# PG03_ECG.net
KiCad netlist of a schematic drawn in Altium Designer
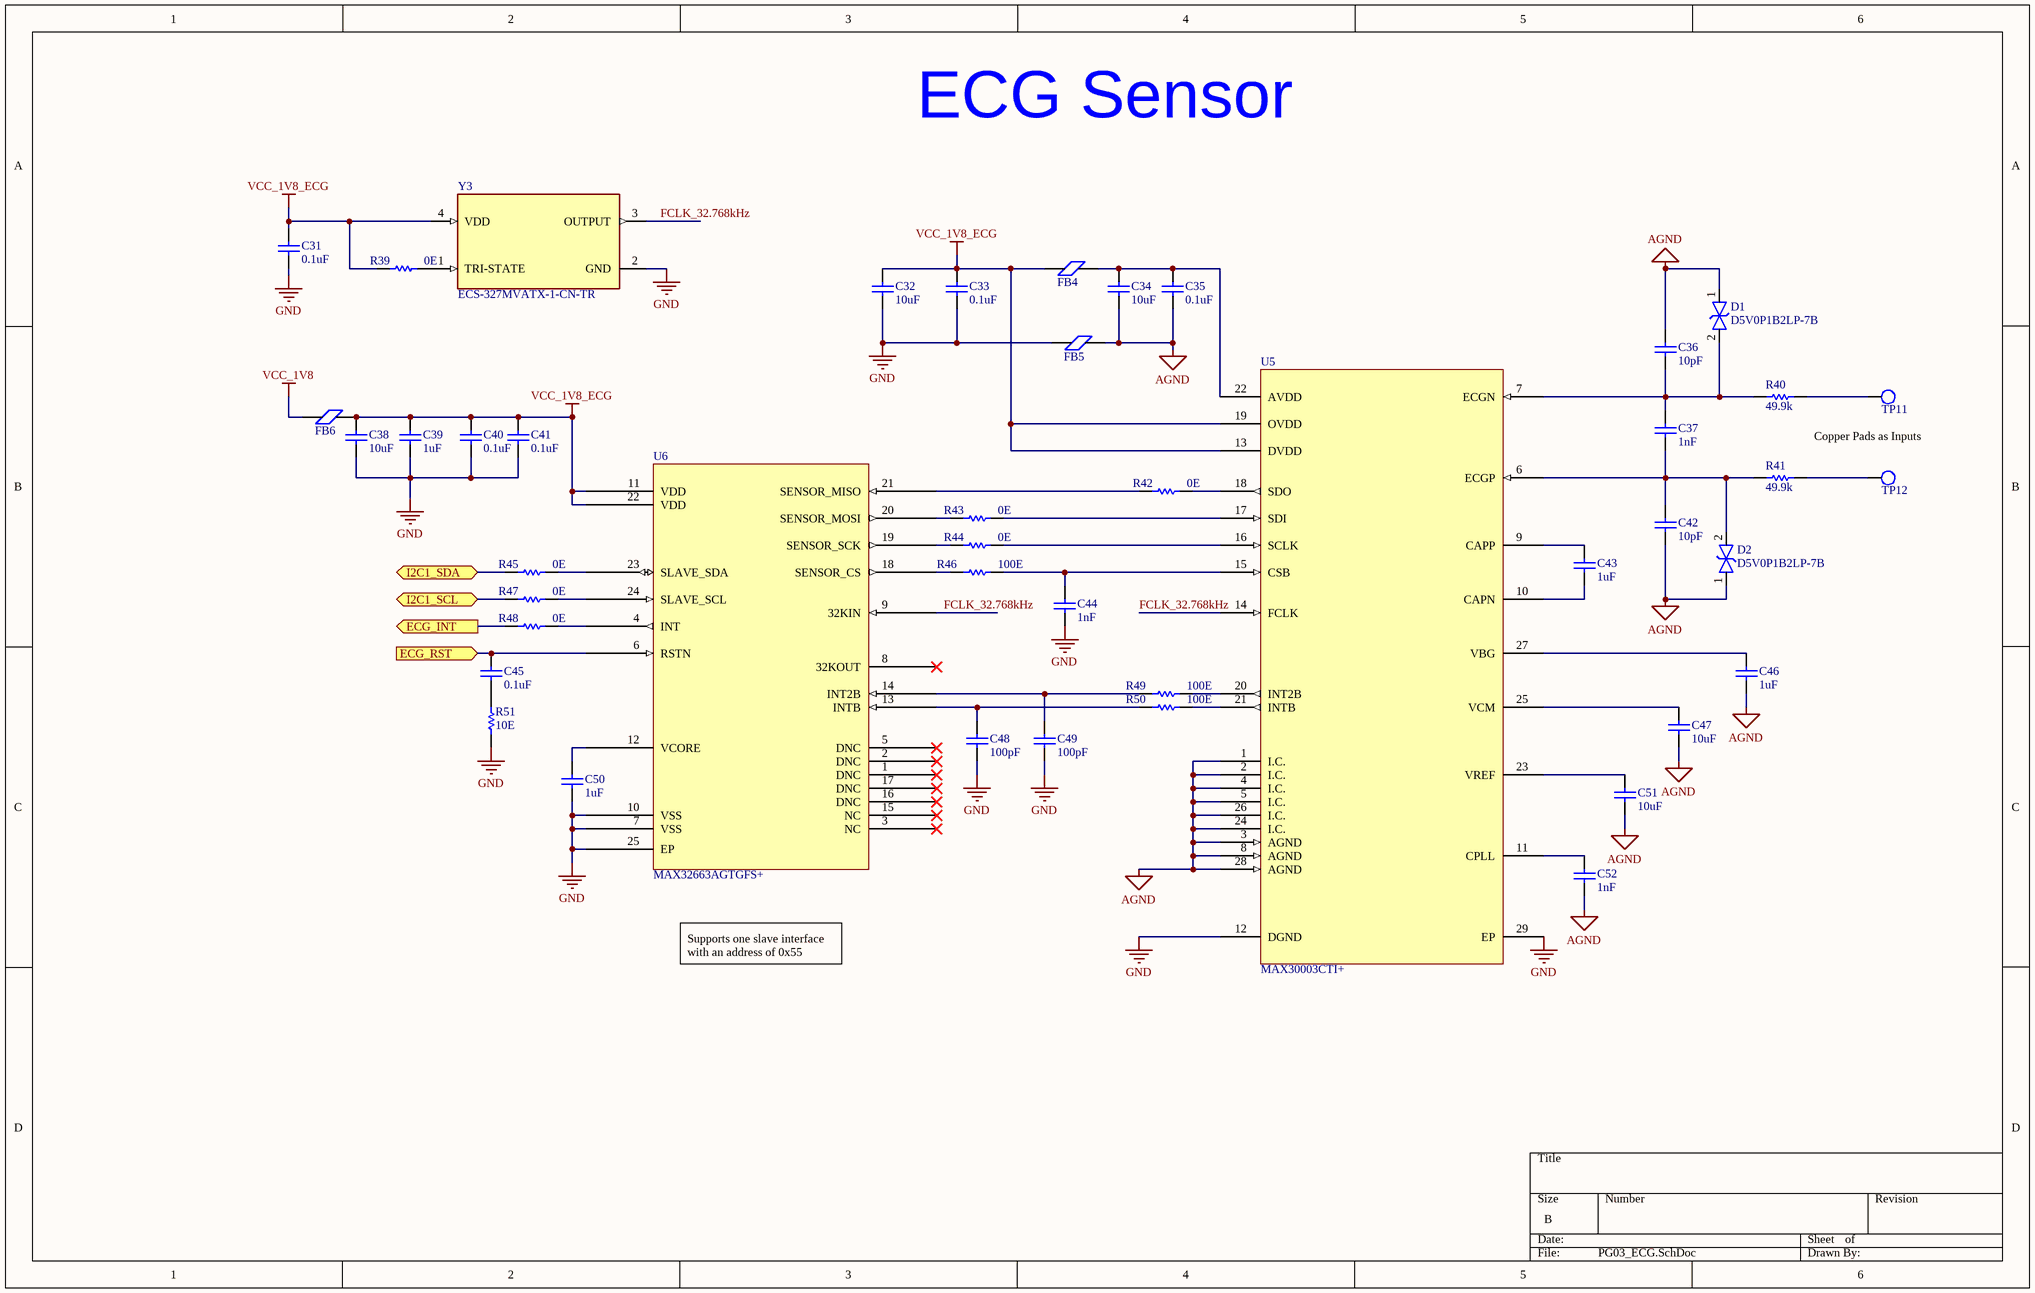
[diagram p0: PG03_ECG.SchDoc]

(export (version "E")
  (design (tool "Eeschema 10.0.6"))
  (components
    (comp (ref "C31")
      (value "0.1uF")
      (footprint "0402C")
      (description "CAP CER 0.1UF 50V X7R 0402")
      (libsource (lib "Smart Ring Components") (part "CAP_0402_0.1uF_50V"))
    )
    (comp (ref "C32")
      (value "10uF")
      (footprint "0805C")
      (description "CAP CER 10UF 16V X7R 0805")
      (libsource (lib "Smart Ring Components") (part "CAP_0805_10uF_16V"))
    )
    (comp (ref "C33")
      (value "0.1uF")
      (footprint "0402C")
      (description "CAP CER 0.1UF 50V X7R 0402")
      (libsource (lib "Smart Ring Components") (part "CAP_0402_0.1uF_50V"))
    )
    (comp (ref "C34")
      (value "10uF")
      (footprint "0805C")
      (description "CAP CER 10UF 16V X7R 0805")
      (libsource (lib "Smart Ring Components") (part "CAP_0805_10uF_16V"))
    )
    (comp (ref "C35")
      (value "0.1uF")
      (footprint "0402C")
      (description "CAP CER 0.1UF 50V X7R 0402")
      (libsource (lib "Smart Ring Components") (part "CAP_0402_0.1uF_50V"))
    )
    (comp (ref "C36")
      (value "10pF")
      (footprint "0402C")
      (description "CAP CER 10PF 50V C0G/NP0 0402")
      (libsource (lib "Smart Ring Components") (part "CAP_0402_10pF_50V"))
    )
    (comp (ref "C37")
      (value "1nF")
      (footprint "0402C")
      (description "CAP CER 1000PF 50V X7R 0402")
      (libsource (lib "Smart Ring Components") (part "CAP_0402_1nF_50V"))
    )
    (comp (ref "C38")
      (value "10uF")
      (footprint "0805C")
      (description "CAP CER 10UF 16V X7R 0805")
      (libsource (lib "Smart Ring Components") (part "CAP_0805_10uF_16V"))
    )
    (comp (ref "C39")
      (value "1uF")
      (footprint "0805C")
      (description "CAP CER 1UF 25V X7R 0805")
      (libsource (lib "Smart Ring Components") (part "CAP_0805_1uF_25V"))
    )
    (comp (ref "C40")
      (value "0.1uF")
      (footprint "0402C")
      (description "CAP CER 0.1UF 50V X7R 0402")
      (libsource (lib "Smart Ring Components") (part "CAP_0402_0.1uF_50V"))
    )
    (comp (ref "C41")
      (value "0.1uF")
      (footprint "0402C")
      (description "CAP CER 0.1UF 50V X7R 0402")
      (libsource (lib "Smart Ring Components") (part "CAP_0402_0.1uF_50V"))
    )
    (comp (ref "C42")
      (value "10pF")
      (footprint "0402C")
      (description "CAP CER 10PF 50V C0G/NP0 0402")
      (libsource (lib "Smart Ring Components") (part "CAP_0402_10pF_50V"))
    )
    (comp (ref "C43")
      (value "1uF")
      (footprint "0805C")
      (description "CAP CER 1UF 25V X7R 0805")
      (libsource (lib "Smart Ring Components") (part "CAP_0805_1uF_25V"))
    )
    (comp (ref "C44")
      (value "1nF")
      (footprint "0402C")
      (description "CAP CER 1000PF 50V X7R 0402")
      (libsource (lib "Smart Ring Components") (part "CAP_0402_1nF_50V"))
    )
    (comp (ref "C45")
      (value "0.1uF")
      (footprint "0402C")
      (description "CAP CER 0.1UF 50V X7R 0402")
      (libsource (lib "Smart Ring Components") (part "CAP_0402_0.1uF_50V"))
    )
    (comp (ref "C46")
      (value "1uF")
      (footprint "0805C")
      (description "CAP CER 1UF 25V X7R 0805")
      (libsource (lib "Smart Ring Components") (part "CAP_0805_1uF_25V"))
    )
    (comp (ref "C47")
      (value "10uF")
      (footprint "0805C")
      (description "CAP CER 10UF 16V X7R 0805")
      (libsource (lib "Smart Ring Components") (part "CAP_0805_10uF_16V"))
    )
    (comp (ref "C48")
      (value "100pF")
      (footprint "0402C")
      (description "CAP CER 100PF 50V C0G 0402")
      (libsource (lib "Smart Ring Components") (part "CAP_0402_100pF_50V"))
    )
    (comp (ref "C49")
      (value "100pF")
      (footprint "0402C")
      (description "CAP CER 100PF 50V C0G 0402")
      (libsource (lib "Smart Ring Components") (part "CAP_0402_100pF_50V"))
    )
    (comp (ref "C50")
      (value "1uF")
      (footprint "0805C")
      (description "CAP CER 1UF 25V X7R 0805")
      (libsource (lib "Smart Ring Components") (part "CAP_0805_1uF_25V"))
    )
    (comp (ref "C51")
      (value "10uF")
      (footprint "0805C")
      (description "CAP CER 10UF 16V X7R 0805")
      (libsource (lib "Smart Ring Components") (part "CAP_0805_10uF_16V"))
    )
    (comp (ref "C52")
      (value "1nF")
      (footprint "0402C")
      (description "CAP CER 1000PF 50V X7R 0402")
      (libsource (lib "Smart Ring Components") (part "CAP_0402_1nF_50V"))
    )
    (comp (ref "D1")
      (value "D5V0P1B2LP-7B")
      (footprint "D5V0P1B2LP-7B")
      (description "TVS DIODE 5.5VWM 13VC DFN1006-2")
      (fields (field (name "MFR") "Diodes Incorporated"))
      (libsource (lib "Smart Ring Components") (part "TVS_D5V0P1B2LP-7B"))
    )
    (comp (ref "D2")
      (value "D5V0P1B2LP-7B")
      (footprint "D5V0P1B2LP-7B")
      (description "TVS DIODE 5.5VWM 13VC DFN1006-2")
      (fields (field (name "MFR") "Diodes Incorporated"))
      (libsource (lib "Smart Ring Components") (part "TVS_D5V0P1B2LP-7B"))
    )
    (comp (ref "FB4")
      (value "Ferrite Bead")
      (footprint "0402R")
      (description "CHIP BEAD 600 OHM 0402 300mA")
      (fields (field (name "MFR") "Walsin") (field (name "MPN") "WLBD1005K2U601TP"))
      (libsource (lib "Smart Ring Components") (part "Ferrite Bead"))
    )
    (comp (ref "FB5")
      (value "Ferrite Bead")
      (footprint "0402R")
      (description "CHIP BEAD 600 OHM 0402 300mA")
      (fields (field (name "MFR") "Walsin") (field (name "MPN") "WLBD1005K2U601TP"))
      (libsource (lib "Smart Ring Components") (part "Ferrite Bead"))
    )
    (comp (ref "FB6")
      (value "Ferrite Bead")
      (footprint "0402R")
      (description "CHIP BEAD 600 OHM 0402 300mA")
      (fields (field (name "MFR") "Walsin") (field (name "MPN") "WLBD1005K2U601TP"))
      (libsource (lib "Smart Ring Components") (part "Ferrite Bead"))
    )
    (comp (ref "R39")
      (value "0E")
      (footprint "0402R")
      (description "RES 0 OHM JUMPER 1/16W 0402")
      (fields (field (name "MFR") "Generic"))
      (libsource (lib "Smart Ring Components") (part "RES_0402_0E"))
    )
    (comp (ref "R40")
      (value "49.9k")
      (footprint "0402R")
      (description "RES 49.9K OHM 1% 1/16W 0402")
      (fields (field (name "MFR") "Generic"))
      (libsource (lib "Smart Ring Components") (part "RES_0402_49.9k"))
    )
    (comp (ref "R41")
      (value "49.9k")
      (footprint "0402R")
      (description "RES 49.9K OHM 1% 1/16W 0402")
      (fields (field (name "MFR") "Generic"))
      (libsource (lib "Smart Ring Components") (part "RES_0402_49.9k"))
    )
    (comp (ref "R42")
      (value "0E")
      (footprint "0402R")
      (description "RES 0 OHM JUMPER 1/16W 0402")
      (fields (field (name "MFR") "Generic"))
      (libsource (lib "Smart Ring Components") (part "RES_0402_0E"))
    )
    (comp (ref "R43")
      (value "0E")
      (footprint "0402R")
      (description "RES 0 OHM JUMPER 1/16W 0402")
      (fields (field (name "MFR") "Generic"))
      (libsource (lib "Smart Ring Components") (part "RES_0402_0E"))
    )
    (comp (ref "R44")
      (value "0E")
      (footprint "0402R")
      (description "RES 0 OHM JUMPER 1/16W 0402")
      (fields (field (name "MFR") "Generic"))
      (libsource (lib "Smart Ring Components") (part "RES_0402_0E"))
    )
    (comp (ref "R45")
      (value "0E")
      (footprint "0402R")
      (description "RES 0 OHM JUMPER 1/16W 0402")
      (fields (field (name "MFR") "Generic"))
      (libsource (lib "Smart Ring Components") (part "RES_0402_0E"))
    )
    (comp (ref "R46")
      (value "100E")
      (footprint "0402R")
      (description "RES 100 OHM 1% 1/16W 0402")
      (fields (field (name "MFR") "Generic"))
      (libsource (lib "Smart Ring Components") (part "RES_0402_100E"))
    )
    (comp (ref "R47")
      (value "0E")
      (footprint "0402R")
      (description "RES 0 OHM JUMPER 1/16W 0402")
      (fields (field (name "MFR") "Generic"))
      (libsource (lib "Smart Ring Components") (part "RES_0402_0E"))
    )
    (comp (ref "R48")
      (value "0E")
      (footprint "0402R")
      (description "RES 0 OHM JUMPER 1/16W 0402")
      (fields (field (name "MFR") "Generic"))
      (libsource (lib "Smart Ring Components") (part "RES_0402_0E"))
    )
    (comp (ref "R49")
      (value "100E")
      (footprint "0402R")
      (description "RES 100 OHM 1% 1/16W 0402")
      (fields (field (name "MFR") "Generic"))
      (libsource (lib "Smart Ring Components") (part "RES_0402_100E"))
    )
    (comp (ref "R50")
      (value "100E")
      (footprint "0402R")
      (description "RES 100 OHM 1% 1/16W 0402")
      (fields (field (name "MFR") "Generic"))
      (libsource (lib "Smart Ring Components") (part "RES_0402_100E"))
    )
    (comp (ref "R51")
      (value "10E")
      (footprint "0402R")
      (description "RES 10 OHM 1% 1/16W 0402")
      (fields (field (name "MFR") "Generic"))
      (libsource (lib "Smart Ring Components") (part "RES_0402_10E"))
    )
    (comp (ref "TP11")
      (value "Test_Point")
      (footprint "TP_SMD")
      (libsource (lib "Smart Ring Components") (part "Test_Point_1"))
    )
    (comp (ref "TP12")
      (value "Test_Point")
      (footprint "TP_SMD")
      (libsource (lib "Smart Ring Components") (part "Test_Point_1"))
    )
    (comp (ref "U5")
      (value "MAX30003CTI+")
      (footprint "MAX30003CTI+")
      (description "Analog Front End - AFE Bio Potential AFE")
      (fields (field (name "MFR") "Maxim Integrated") (field (name "MPN") "MAX30003CTI+"))
      (libsource (lib "Smart Ring Components") (part "MAX30003CTI+"))
    )
    (comp (ref "U6")
      (value "MAX32663AGTGFS+")
      (footprint "MAX32663AGTGFS+")
      (description "SENSOR HUB W/ B-SECUR'S FULL HEA")
      (fields (field (name "MFR") "Maxim Integrated"))
      (libsource (lib "Smart Ring Components") (part "MAX32663AGTGFS+"))
    )
    (comp (ref "Y3")
      (value "ECS-327MVATX-1-CN-TR")
      (footprint "ECS-327MVATX-1-CN-TR")
      (description "XTAL OSC XO 32.768KHZ SMD")
      (fields (field (name "MFR") "ECS Inc."))
      (libsource (lib "Smart Ring Components") (part "OSC_32.768kHz"))
    )
  )
  (nets
    (net (code "1") (name "/ECG_INT") (class "Default")
      (node (ref "R48") (pin "1") (pinfunction "1_1") (pintype "passive"))
    )
    (net (code "2") (name "/ECG_RST") (class "Default")
      (node (ref "C45") (pin "2") (pinfunction "2_2") (pintype "passive"))
      (node (ref "U6") (pin "6") (pinfunction "RSTN_6") (pintype "input"))
    )
    (net (code "3") (name "/FCLK_32.768kHz") (class "Default")
      (node (ref "U5") (pin "14") (pinfunction "FCLK_14") (pintype "input"))
      (node (ref "U6") (pin "9") (pinfunction "32KIN_9") (pintype "input"))
      (node (ref "Y3") (pin "3") (pinfunction "OUTPUT_3") (pintype "output"))
    )
    (net (code "4") (name "/I2C1_SCL") (class "Default")
      (node (ref "R47") (pin "1") (pinfunction "1_1") (pintype "passive"))
    )
    (net (code "5") (name "/I2C1_SDA") (class "Default")
      (node (ref "R45") (pin "1") (pinfunction "1_1") (pintype "passive"))
    )
    (net (code "6") (name "AGND") (class "Default")
      (node (ref "C34") (pin "1") (pinfunction "1_1") (pintype "passive"))
      (node (ref "C35") (pin "1") (pinfunction "1_1") (pintype "passive"))
      (node (ref "C36") (pin "2") (pinfunction "2_2") (pintype "passive"))
      (node (ref "C42") (pin "1") (pinfunction "1_1") (pintype "passive"))
      (node (ref "C46") (pin "1") (pinfunction "1_1") (pintype "passive"))
      (node (ref "C47") (pin "1") (pinfunction "1_1") (pintype "passive"))
      (node (ref "C51") (pin "1") (pinfunction "1_1") (pintype "passive"))
      (node (ref "C52") (pin "1") (pinfunction "1_1") (pintype "passive"))
      (node (ref "D1") (pin "1") (pinfunction "1_1") (pintype "passive"))
      (node (ref "D2") (pin "1") (pinfunction "1_1") (pintype "passive"))
      (node (ref "FB5") (pin "2") (pinfunction "VREF_2") (pintype "passive"))
      (node (ref "U5") (pin "1") (pinfunction "I.C._1") (pintype "passive"))
      (node (ref "U5") (pin "2") (pinfunction "I.C._2") (pintype "passive"))
      (node (ref "U5") (pin "24") (pinfunction "I.C._24") (pintype "passive"))
      (node (ref "U5") (pin "26") (pinfunction "I.C._26") (pintype "power_in"))
      (node (ref "U5") (pin "28") (pinfunction "AGND_28") (pintype "input"))
      (node (ref "U5") (pin "3") (pinfunction "AGND_3") (pintype "input"))
      (node (ref "U5") (pin "4") (pinfunction "I.C._4") (pintype "passive"))
      (node (ref "U5") (pin "5") (pinfunction "I.C._5") (pintype "passive"))
      (node (ref "U5") (pin "8") (pinfunction "AGND_8") (pintype "input"))
    )
    (net (code "7") (name "GND") (class "Default")
      (node (ref "C31") (pin "1") (pinfunction "1_1") (pintype "passive"))
      (node (ref "C32") (pin "1") (pinfunction "1_1") (pintype "passive"))
      (node (ref "C33") (pin "1") (pinfunction "1_1") (pintype "passive"))
      (node (ref "C38") (pin "1") (pinfunction "1_1") (pintype "passive"))
      (node (ref "C39") (pin "1") (pinfunction "1_1") (pintype "passive"))
      (node (ref "C40") (pin "1") (pinfunction "1_1") (pintype "passive"))
      (node (ref "C41") (pin "1") (pinfunction "1_1") (pintype "passive"))
      (node (ref "C44") (pin "1") (pinfunction "1_1") (pintype "passive"))
      (node (ref "C48") (pin "1") (pinfunction "1_1") (pintype "passive"))
      (node (ref "C49") (pin "1") (pinfunction "1_1") (pintype "passive"))
      (node (ref "C50") (pin "1") (pinfunction "1_1") (pintype "passive"))
      (node (ref "FB5") (pin "1") (pinfunction "VREF_1") (pintype "passive"))
      (node (ref "R51") (pin "1") (pinfunction "1_1") (pintype "passive"))
      (node (ref "U5") (pin "12") (pinfunction "DGND_12") (pintype "power_in"))
      (node (ref "U5") (pin "29") (pinfunction "EP_29") (pintype "power_in"))
      (node (ref "U6") (pin "10") (pinfunction "VSS_10") (pintype "power_in"))
      (node (ref "U6") (pin "25") (pinfunction "EP_25") (pintype "power_in"))
      (node (ref "U6") (pin "7") (pinfunction "VSS_7") (pintype "power_in"))
      (node (ref "Y3") (pin "2") (pinfunction "GND_2") (pintype "power_in"))
    )
    (net (code "8") (name "Net-(C45-Pad1)") (class "Default")
      (node (ref "C45") (pin "1") (pinfunction "1_1") (pintype "passive"))
      (node (ref "R51") (pin "2") (pinfunction "2_2") (pintype "passive"))
    )
    (net (code "9") (name "Net-(R40-Pad2)") (class "Default")
      (node (ref "R40") (pin "2") (pinfunction "2_2") (pintype "passive"))
      (node (ref "TP11") (pin "1") (pintype "passive"))
    )
    (net (code "10") (name "Net-(R41-Pad2)") (class "Default")
      (node (ref "R41") (pin "2") (pinfunction "2_2") (pintype "passive"))
      (node (ref "TP12") (pin "1") (pintype "passive"))
    )
    (net (code "11") (name "Net-(U5-AVDD)") (class "Default")
      (node (ref "C34") (pin "2") (pinfunction "2_2") (pintype "passive"))
      (node (ref "C35") (pin "2") (pinfunction "2_2") (pintype "passive"))
      (node (ref "FB4") (pin "1") (pinfunction "VREF_1") (pintype "passive"))
      (node (ref "U5") (pin "22") (pinfunction "AVDD_22") (pintype "power_in"))
    )
    (net (code "12") (name "Net-(U5-CAPN)") (class "Default")
      (node (ref "C43") (pin "1") (pinfunction "1_1") (pintype "passive"))
      (node (ref "U5") (pin "10") (pinfunction "CAPN_10") (pintype "passive"))
    )
    (net (code "13") (name "Net-(U5-CAPP)") (class "Default")
      (node (ref "C43") (pin "2") (pinfunction "2_2") (pintype "passive"))
      (node (ref "U5") (pin "9") (pinfunction "CAPP_9") (pintype "passive"))
    )
    (net (code "14") (name "Net-(U5-CPLL)") (class "Default")
      (node (ref "C52") (pin "2") (pinfunction "2_2") (pintype "passive"))
      (node (ref "U5") (pin "11") (pinfunction "CPLL_11") (pintype "passive"))
    )
    (net (code "15") (name "Net-(U5-CSB)") (class "Default")
      (node (ref "C44") (pin "2") (pinfunction "2_2") (pintype "passive"))
      (node (ref "R46") (pin "2") (pinfunction "2_2") (pintype "passive"))
      (node (ref "U5") (pin "15") (pinfunction "CSB_15") (pintype "input"))
    )
    (net (code "16") (name "Net-(U5-ECGN)") (class "Default")
      (node (ref "C36") (pin "1") (pinfunction "1_1") (pintype "passive"))
      (node (ref "C37") (pin "2") (pinfunction "2_2") (pintype "passive"))
      (node (ref "D1") (pin "2") (pinfunction "2_2") (pintype "passive"))
      (node (ref "R40") (pin "1") (pinfunction "1_1") (pintype "passive"))
      (node (ref "U5") (pin "7") (pinfunction "ECGN_7") (pintype "input"))
    )
    (net (code "17") (name "Net-(U5-ECGP)") (class "Default")
      (node (ref "C37") (pin "1") (pinfunction "1_1") (pintype "passive"))
      (node (ref "C42") (pin "2") (pinfunction "2_2") (pintype "passive"))
      (node (ref "D2") (pin "2") (pinfunction "2_2") (pintype "passive"))
      (node (ref "R41") (pin "1") (pinfunction "1_1") (pintype "passive"))
      (node (ref "U5") (pin "6") (pinfunction "ECGP_6") (pintype "input"))
    )
    (net (code "18") (name "Net-(U5-INT2B)") (class "Default")
      (node (ref "R49") (pin "2") (pinfunction "2_2") (pintype "passive"))
      (node (ref "U5") (pin "20") (pinfunction "INT2B_20") (pintype "output"))
    )
    (net (code "19") (name "Net-(U5-INTB)") (class "Default")
      (node (ref "R50") (pin "2") (pinfunction "2_2") (pintype "passive"))
      (node (ref "U5") (pin "21") (pinfunction "INTB_21") (pintype "output"))
    )
    (net (code "20") (name "Net-(U5-SCLK)") (class "Default")
      (node (ref "R44") (pin "2") (pinfunction "2_2") (pintype "passive"))
      (node (ref "U5") (pin "16") (pinfunction "SCLK_16") (pintype "input"))
    )
    (net (code "21") (name "Net-(U5-SDI)") (class "Default")
      (node (ref "R43") (pin "2") (pinfunction "2_2") (pintype "passive"))
      (node (ref "U5") (pin "17") (pinfunction "SDI_17") (pintype "input"))
    )
    (net (code "22") (name "Net-(U5-SDO)") (class "Default")
      (node (ref "R42") (pin "2") (pinfunction "2_2") (pintype "passive"))
      (node (ref "U5") (pin "18") (pinfunction "SDO_18") (pintype "output"))
    )
    (net (code "23") (name "Net-(U5-VBG)") (class "Default")
      (node (ref "C46") (pin "2") (pinfunction "2_2") (pintype "passive"))
      (node (ref "U5") (pin "27") (pinfunction "VBG_27") (pintype "passive"))
    )
    (net (code "24") (name "Net-(U5-VCM)") (class "Default")
      (node (ref "C47") (pin "2") (pinfunction "2_2") (pintype "passive"))
      (node (ref "U5") (pin "25") (pinfunction "VCM_25") (pintype "passive"))
    )
    (net (code "25") (name "Net-(U5-VREF)") (class "Default")
      (node (ref "C51") (pin "2") (pinfunction "2_2") (pintype "passive"))
      (node (ref "U5") (pin "23") (pinfunction "VREF_23") (pintype "passive"))
    )
    (net (code "26") (name "Net-(U6-INT)") (class "Default")
      (node (ref "R48") (pin "2") (pinfunction "2_2") (pintype "passive"))
      (node (ref "U6") (pin "4") (pinfunction "INT_4") (pintype "output"))
    )
    (net (code "27") (name "Net-(U6-INT2B)") (class "Default")
      (node (ref "C49") (pin "2") (pinfunction "2_2") (pintype "passive"))
      (node (ref "R49") (pin "1") (pinfunction "1_1") (pintype "passive"))
      (node (ref "U6") (pin "14") (pinfunction "INT2B_14") (pintype "input"))
    )
    (net (code "28") (name "Net-(U6-INTB)") (class "Default")
      (node (ref "C48") (pin "2") (pinfunction "2_2") (pintype "passive"))
      (node (ref "R50") (pin "1") (pinfunction "1_1") (pintype "passive"))
      (node (ref "U6") (pin "13") (pinfunction "INTB_13") (pintype "input"))
    )
    (net (code "29") (name "Net-(U6-SENSOR_CS)") (class "Default")
      (node (ref "R46") (pin "1") (pinfunction "1_1") (pintype "passive"))
      (node (ref "U6") (pin "18") (pinfunction "SENSOR_CS_18") (pintype "output"))
    )
    (net (code "30") (name "Net-(U6-SENSOR_MISO)") (class "Default")
      (node (ref "R42") (pin "1") (pinfunction "1_1") (pintype "passive"))
      (node (ref "U6") (pin "21") (pinfunction "SENSOR_MISO_21") (pintype "input"))
    )
    (net (code "31") (name "Net-(U6-SENSOR_MOSI)") (class "Default")
      (node (ref "R43") (pin "1") (pinfunction "1_1") (pintype "passive"))
      (node (ref "U6") (pin "20") (pinfunction "SENSOR_MOSI_20") (pintype "output"))
    )
    (net (code "32") (name "Net-(U6-SENSOR_SCK)") (class "Default")
      (node (ref "R44") (pin "1") (pinfunction "1_1") (pintype "passive"))
      (node (ref "U6") (pin "19") (pinfunction "SENSOR_SCK_19") (pintype "output"))
    )
    (net (code "33") (name "Net-(U6-SLAVE_SCL)") (class "Default")
      (node (ref "R47") (pin "2") (pinfunction "2_2") (pintype "passive"))
      (node (ref "U6") (pin "24") (pinfunction "SLAVE_SCL_24") (pintype "input"))
    )
    (net (code "34") (name "Net-(U6-SLAVE_SDA)") (class "Default")
      (node (ref "R45") (pin "2") (pinfunction "2_2") (pintype "passive"))
      (node (ref "U6") (pin "23") (pinfunction "SLAVE_SDA_23") (pintype "bidirectional"))
    )
    (net (code "35") (name "Net-(U6-VCORE)") (class "Default")
      (node (ref "C50") (pin "2") (pinfunction "2_2") (pintype "passive"))
      (node (ref "U6") (pin "12") (pinfunction "VCORE_12") (pintype "power_in"))
    )
    (net (code "36") (name "Net-(Y3-TRI-STATE)") (class "Default")
      (node (ref "R39") (pin "2") (pinfunction "2_2") (pintype "passive"))
      (node (ref "Y3") (pin "1") (pinfunction "TRI-STATE_1") (pintype "input"))
    )
    (net (code "37") (name "VCC_1V8") (class "Default")
      (node (ref "FB6") (pin "2") (pinfunction "VREF_2") (pintype "passive"))
    )
    (net (code "38") (name "VCC_1V8_ECG") (class "Default")
      (node (ref "C31") (pin "2") (pinfunction "2_2") (pintype "passive"))
      (node (ref "C32") (pin "2") (pinfunction "2_2") (pintype "passive"))
      (node (ref "C33") (pin "2") (pinfunction "2_2") (pintype "passive"))
      (node (ref "C38") (pin "2") (pinfunction "2_2") (pintype "passive"))
      (node (ref "C39") (pin "2") (pinfunction "2_2") (pintype "passive"))
      (node (ref "C40") (pin "2") (pinfunction "2_2") (pintype "passive"))
      (node (ref "C41") (pin "2") (pinfunction "2_2") (pintype "passive"))
      (node (ref "FB4") (pin "2") (pinfunction "VREF_2") (pintype "passive"))
      (node (ref "FB6") (pin "1") (pinfunction "VREF_1") (pintype "passive"))
      (node (ref "R39") (pin "1") (pinfunction "1_1") (pintype "passive"))
      (node (ref "U5") (pin "13") (pinfunction "DVDD_13") (pintype "power_in"))
      (node (ref "U5") (pin "19") (pinfunction "OVDD_19") (pintype "power_in"))
      (node (ref "U6") (pin "11") (pinfunction "VDD_11") (pintype "power_in"))
      (node (ref "U6") (pin "22") (pinfunction "VDD_22") (pintype "power_in"))
      (node (ref "Y3") (pin "4") (pinfunction "VDD_4") (pintype "input"))
    )
    (net (code "39") (name "unconnected-(U6-32KOUT-Pad8)") (class "Default")
      (node (ref "U6") (pin "8") (pinfunction "32KOUT_8") (pintype "passive+no_connect"))
    )
    (net (code "40") (name "unconnected-(U6-DNC-Pad1)") (class "Default")
      (node (ref "U6") (pin "1") (pinfunction "DNC_1") (pintype "passive+no_connect"))
    )
    (net (code "41") (name "unconnected-(U6-DNC-Pad2)") (class "Default")
      (node (ref "U6") (pin "2") (pinfunction "DNC_2") (pintype "passive+no_connect"))
    )
    (net (code "42") (name "unconnected-(U6-DNC-Pad5)") (class "Default")
      (node (ref "U6") (pin "5") (pinfunction "DNC_5") (pintype "passive+no_connect"))
    )
    (net (code "43") (name "unconnected-(U6-DNC-Pad16)") (class "Default")
      (node (ref "U6") (pin "16") (pinfunction "DNC_16") (pintype "passive+no_connect"))
    )
    (net (code "44") (name "unconnected-(U6-DNC-Pad17)") (class "Default")
      (node (ref "U6") (pin "17") (pinfunction "DNC_17") (pintype "passive+no_connect"))
    )
    (net (code "45") (name "unconnected-(U6-NC-Pad3)") (class "Default")
      (node (ref "U6") (pin "3") (pinfunction "NC_3") (pintype "passive+no_connect"))
    )
    (net (code "46") (name "unconnected-(U6-NC-Pad15)") (class "Default")
      (node (ref "U6") (pin "15") (pinfunction "NC_15") (pintype "passive+no_connect"))
    )
  )
)
